# Sen_PF.net
KiCad netlist of a schematic drawn in Altium Designer
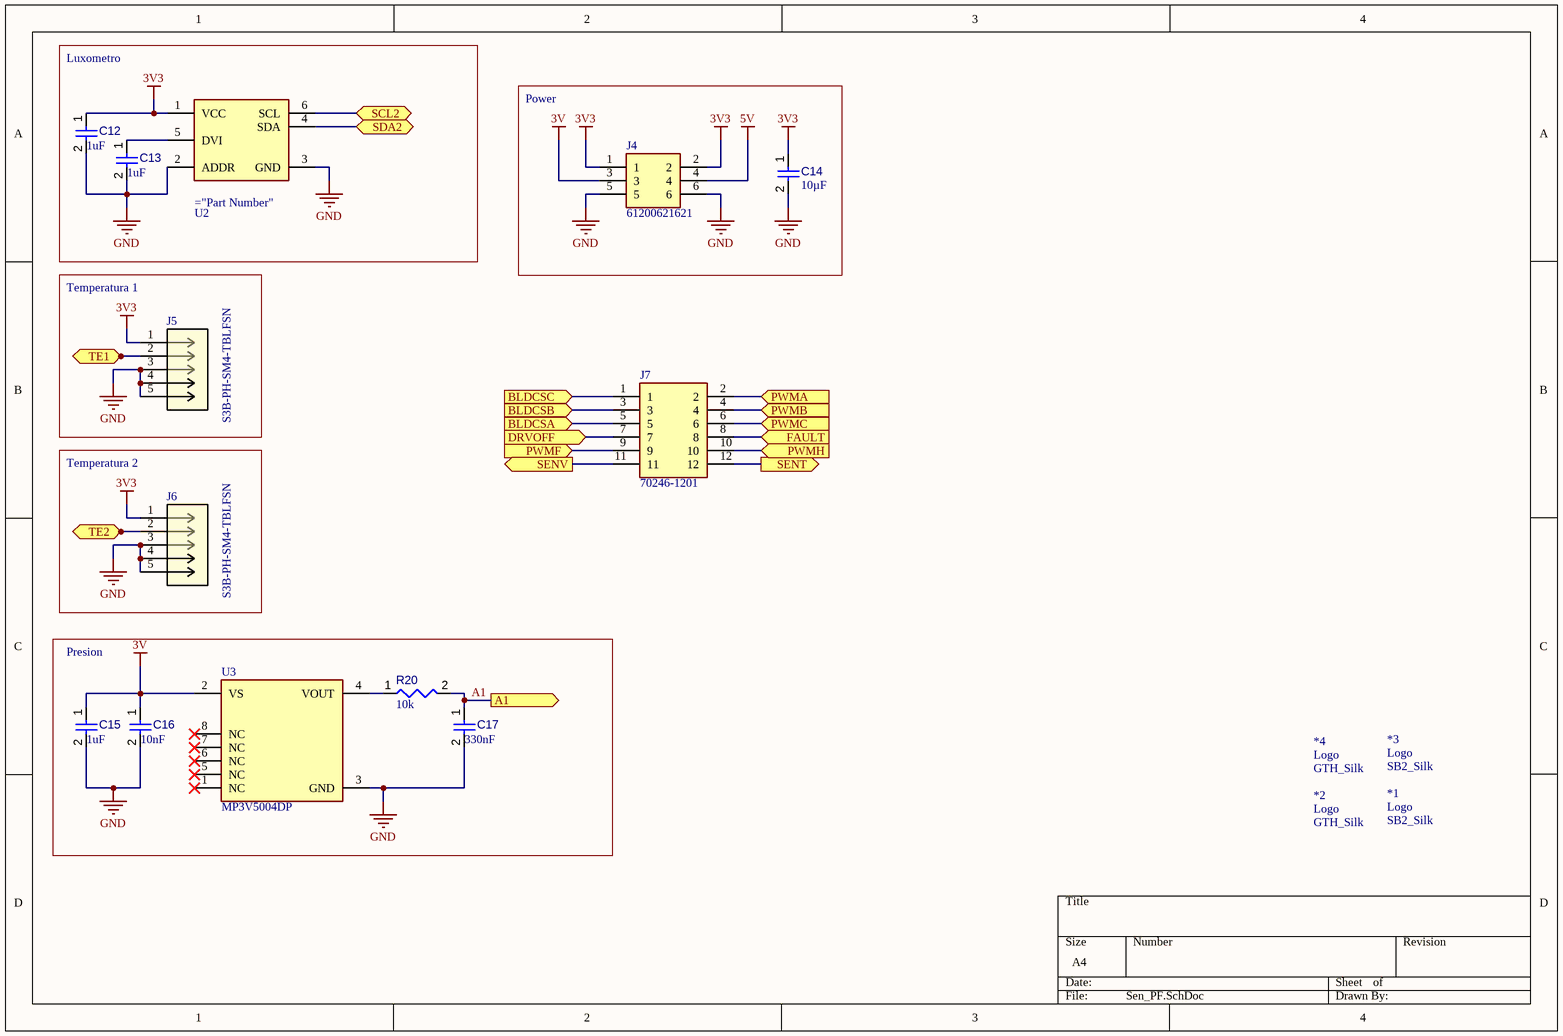
[diagram p0: Sen_PF.SchDoc]

(export (version "E")
  (design (tool "Eeschema 10.0.6"))
  (components
    (comp (ref "*1")
      (value "SB2_Silk")
      (footprint "SMARTBEDDING2_SILK")
      (libsource (lib "LogoGIBIC") (part "SB2_Silk"))
    )
    (comp (ref "*2")
      (value "GTH_Silk")
      (footprint "TECHHUB_SILK")
      (libsource (lib "LogoGIBIC") (part "GTH_Silk"))
    )
    (comp (ref "*3")
      (value "SB2_Silk")
      (footprint "SMARTBEDDING2_SILK")
      (libsource (lib "LogoGIBIC") (part "SB2_Silk"))
    )
    (comp (ref "*4")
      (value "GTH_Silk")
      (footprint "TECHHUB_SILK")
      (libsource (lib "LogoGIBIC") (part "GTH_Silk"))
    )
    (comp (ref "C12")
      (value "1uF")
      (footprint "CAPC1608X90X40NL10T20")
      (description "Chip Capacitor, 100 nF, +/- 10%, 50 V, 0603 (1608 Metric)")
      (fields (field (name "TOLERANCE") "10%") (field (name "Comment") "Capacitor 100 nF +/-10% 50 V 0603"))
      (libsource (lib "UdeA") (part "CAP-NP-2"))
    )
    (comp (ref "C13")
      (value "1uF")
      (footprint "CAPC1608X90X40NL10T20")
      (description "Chip Capacitor, 100 nF, +/- 10%, 50 V, 0603 (1608 Metric)")
      (fields (field (name "TOLERANCE") "10%") (field (name "Comment") "Capacitor 100 nF +/-10% 50 V 0603"))
      (libsource (lib "UdeA") (part "CAP-NP-2"))
    )
    (comp (ref "C14")
      (value "10µF")
      (footprint "CAPC0805(2012)145_L")
      (description "Chip Capacitor, 22µF +/-40%, 16V, 0805, Thickness 1.45 mm")
      (fields (field (name "TOLERANCE") "5%") (field (name "Comment") "Capacitor 22µF +/-40% 16V 0805"))
      (libsource (lib "UdeA") (part "CAP-NP-2"))
    )
    (comp (ref "C15")
      (value "1uF")
      (footprint "CAPC1608X90X40NL10T20")
      (description "Chip Capacitor, 100 nF, +/- 10%, 50 V, 0603 (1608 Metric)")
      (fields (field (name "TOLERANCE") "10%") (field (name "Comment") "Capacitor 100 nF +/-10% 50 V 0603"))
      (libsource (lib "UdeA") (part "CAP-NP-2"))
    )
    (comp (ref "C16")
      (value "10nF")
      (footprint "CAPC1608X90X40NL10T20")
      (description "Chip Capacitor, 100 nF, +/- 10%, 50 V, 0603 (1608 Metric)")
      (fields (field (name "TOLERANCE") "10%") (field (name "Comment") "Capacitor 100 nF +/-10% 50 V 0603"))
      (libsource (lib "UdeA") (part "CAP-NP-2"))
    )
    (comp (ref "C17")
      (value "330nF")
      (footprint "CAPC1608X90X40NL10T20")
      (description "Chip Capacitor, 100 nF, +/- 10%, 50 V, 0603 (1608 Metric)")
      (fields (field (name "TOLERANCE") "10%") (field (name "Comment") "Capacitor 100 nF +/-10% 50 V 0603"))
      (libsource (lib "UdeA") (part "CAP-NP-2"))
    )
    (comp (ref "J4")
      (value "61200621621")
      (footprint "SHDR6W64P254_2X3_1528X910X910P")
      (description "Wurth Elektronik PCB Header WR-BHD, 6 Way, 2.54mm Pitch, 2 Row, Straight, Through Hole")
      (fields (field (name "MOUSER PART NUMBER") "710-61200621621"))
      (libsource (lib "61200621621") (part "61200621621"))
    )
    (comp (ref "J5")
      (value "S3B-PH-SM4-TBLFSN")
      (footprint "CONN_S3B-PH-SM4-TBLFSN_JST")
      (description "No Description Available")
      (libsource (lib "S3B-PH-SM4-TBLFSN") (part "S3B-PH-SM4-TBLFSN"))
    )
    (comp (ref "J6")
      (value "S3B-PH-SM4-TBLFSN")
      (footprint "CONN_S3B-PH-SM4-TBLFSN_JST")
      (description "No Description Available")
      (libsource (lib "S3B-PH-SM4-TBLFSN") (part "S3B-PH-SM4-TBLFSN"))
    )
    (comp (ref "J7")
      (value "70246-1201")
      (footprint "SHDR12W99P254_2X6_2286X889X927P")
      (fields (field (name "MOUSER PART NUMBER") "538-70246-1201"))
      (libsource (lib "70246-1201") (part "70246-1201"))
    )
    (comp (ref "R20")
      (value "10k")
      (footprint "RESC1608X55X25ML10T15")
      (description "Chip Resistor, 10 KOhm, +/- 1%, 01 W, -55 to 155 degC, 0603 (1608 Metric)")
      (fields (field (name "POWER") "100mW") (field (name "TOLERANCE") "1%"))
      (libsource (lib "UdeA") (part "RES-2"))
    )
    (comp (ref "U2")
      (value "BH1750FVI-TR")
      (footprint "ROHM_BH1750FVI-TR_0")
      (description "BH1730FVI-TR")
      (libsource (lib "IC_ROHM_BH1750FVI-TR_eec") (part "BH1750FVI-TR"))
    )
    (comp (ref "U3")
      (value "MP3V5004DP")
      (footprint "Freescale_Semiconductor_SOT1693-1_MFG")
      (fields
        (field (name "DIGIKEY PART NUMBER") "MP3V5004DP-ND")
        (field (name "MOUSER PART NUMBER") "841-MP3V5004DP")
        (field (name "MANUFACTURER") "Freescale Semiconductor")
      )
      (libsource (lib "UdeA") (part "MP3V5004DP"))
    )
  )
  (nets
    (net (code "1") (name "/A1") (class "Default")
      (node (ref "C17") (pin "1") (pinfunction "1_1") (pintype "passive"))
      (node (ref "R20") (pin "2") (pinfunction "2_2") (pintype "passive"))
    )
    (net (code "2") (name "/BLDCSA") (class "Default")
      (node (ref "J7") (pin "5") (pinfunction "5_5") (pintype "passive"))
    )
    (net (code "3") (name "/BLDCSB") (class "Default")
      (node (ref "J7") (pin "3") (pinfunction "3_3") (pintype "passive"))
    )
    (net (code "4") (name "/BLDCSC") (class "Default")
      (node (ref "J7") (pin "1") (pinfunction "1_1") (pintype "passive"))
    )
    (net (code "5") (name "/DRVOFF") (class "Default")
      (node (ref "J7") (pin "7") (pinfunction "7_7") (pintype "passive"))
    )
    (net (code "6") (name "/FAULT") (class "Default")
      (node (ref "J7") (pin "8") (pinfunction "8_8") (pintype "passive"))
    )
    (net (code "7") (name "/PWMA") (class "Default")
      (node (ref "J7") (pin "2") (pinfunction "2_2") (pintype "passive"))
    )
    (net (code "8") (name "/PWMB") (class "Default")
      (node (ref "J7") (pin "4") (pinfunction "4_4") (pintype "passive"))
    )
    (net (code "9") (name "/PWMC") (class "Default")
      (node (ref "J7") (pin "6") (pinfunction "6_6") (pintype "passive"))
    )
    (net (code "10") (name "/PWMF") (class "Default")
      (node (ref "J7") (pin "9") (pinfunction "9_9") (pintype "passive"))
    )
    (net (code "11") (name "/PWMH") (class "Default")
      (node (ref "J7") (pin "10") (pinfunction "10_10") (pintype "passive"))
    )
    (net (code "12") (name "/SCL2") (class "Default")
      (node (ref "U2") (pin "6") (pinfunction "SCL_6") (pintype "passive"))
    )
    (net (code "13") (name "/SDA2") (class "Default")
      (node (ref "U2") (pin "4") (pinfunction "SDA_4") (pintype "passive"))
    )
    (net (code "14") (name "/SENT") (class "Default")
      (node (ref "J7") (pin "12") (pinfunction "12_12") (pintype "passive"))
    )
    (net (code "15") (name "/SENV") (class "Default")
      (node (ref "J7") (pin "11") (pinfunction "11_11") (pintype "passive"))
    )
    (net (code "16") (name "/TE1") (class "Default")
      (node (ref "J5") (pin "2") (pinfunction "2_2") (pintype "passive"))
    )
    (net (code "17") (name "/TE2") (class "Default")
      (node (ref "J6") (pin "2") (pinfunction "2_2") (pintype "passive"))
    )
    (net (code "18") (name "3V") (class "Default")
      (node (ref "C15") (pin "1") (pinfunction "1_1") (pintype "passive"))
      (node (ref "C16") (pin "1") (pinfunction "1_1") (pintype "passive"))
      (node (ref "J4") (pin "3") (pinfunction "3_3") (pintype "passive"))
      (node (ref "U3") (pin "2") (pinfunction "VS_2") (pintype "power_in"))
    )
    (net (code "19") (name "3V3") (class "Default")
      (node (ref "C12") (pin "1") (pinfunction "1_1") (pintype "passive"))
      (node (ref "C14") (pin "1") (pinfunction "1_1") (pintype "passive"))
      (node (ref "J4") (pin "1") (pinfunction "1_1") (pintype "passive"))
      (node (ref "J4") (pin "2") (pinfunction "2_2") (pintype "passive"))
      (node (ref "J5") (pin "1") (pinfunction "1_1") (pintype "passive"))
      (node (ref "J6") (pin "1") (pinfunction "1_1") (pintype "passive"))
      (node (ref "U2") (pin "1") (pinfunction "VCC_1") (pintype "passive"))
    )
    (net (code "20") (name "5V") (class "Default")
      (node (ref "J4") (pin "4") (pinfunction "4_4") (pintype "passive"))
    )
    (net (code "21") (name "GND") (class "Default")
      (node (ref "C12") (pin "2") (pinfunction "2_2") (pintype "passive"))
      (node (ref "C13") (pin "2") (pinfunction "2_2") (pintype "passive"))
      (node (ref "C14") (pin "2") (pinfunction "2_2") (pintype "passive"))
      (node (ref "C15") (pin "2") (pinfunction "2_2") (pintype "passive"))
      (node (ref "C16") (pin "2") (pinfunction "2_2") (pintype "passive"))
      (node (ref "C17") (pin "2") (pinfunction "2_2") (pintype "passive"))
      (node (ref "J4") (pin "5") (pinfunction "5_5") (pintype "passive"))
      (node (ref "J4") (pin "6") (pinfunction "6_6") (pintype "passive"))
      (node (ref "J5") (pin "3") (pinfunction "3_3") (pintype "passive"))
      (node (ref "J5") (pin "4") (pinfunction "4_4") (pintype "passive"))
      (node (ref "J5") (pin "5") (pinfunction "5_5") (pintype "passive"))
      (node (ref "J6") (pin "3") (pinfunction "3_3") (pintype "passive"))
      (node (ref "J6") (pin "4") (pinfunction "4_4") (pintype "passive"))
      (node (ref "J6") (pin "5") (pinfunction "5_5") (pintype "passive"))
      (node (ref "U2") (pin "2") (pinfunction "ADDR_2") (pintype "passive"))
      (node (ref "U2") (pin "3") (pinfunction "GND_3") (pintype "passive"))
      (node (ref "U3") (pin "3") (pinfunction "GND_3") (pintype "power_in"))
    )
    (net (code "22") (name "Net-(U2-DVI)") (class "Default")
      (node (ref "C13") (pin "1") (pinfunction "1_1") (pintype "passive"))
      (node (ref "U2") (pin "5") (pinfunction "DVI_5") (pintype "passive"))
    )
    (net (code "23") (name "Net-(U3-VOUT)") (class "Default")
      (node (ref "R20") (pin "1") (pinfunction "1_1") (pintype "passive"))
      (node (ref "U3") (pin "4") (pinfunction "VOUT_4") (pintype "power_in"))
    )
    (net (code "24") (name "unconnected-(U3-NC-Pad1)") (class "Default")
      (node (ref "U3") (pin "1") (pinfunction "NC_1") (pintype "passive+no_connect"))
    )
    (net (code "25") (name "unconnected-(U3-NC-Pad5)") (class "Default")
      (node (ref "U3") (pin "5") (pinfunction "NC_5") (pintype "passive+no_connect"))
    )
    (net (code "26") (name "unconnected-(U3-NC-Pad6)") (class "Default")
      (node (ref "U3") (pin "6") (pinfunction "NC_6") (pintype "passive+no_connect"))
    )
    (net (code "27") (name "unconnected-(U3-NC-Pad7)") (class "Default")
      (node (ref "U3") (pin "7") (pinfunction "NC_7") (pintype "passive+no_connect"))
    )
    (net (code "28") (name "unconnected-(U3-NC-Pad8)") (class "Default")
      (node (ref "U3") (pin "8") (pinfunction "NC_8") (pintype "passive+no_connect"))
    )
  )
)
